# Top.net
KiCad netlist of a schematic drawn in Altium Designer
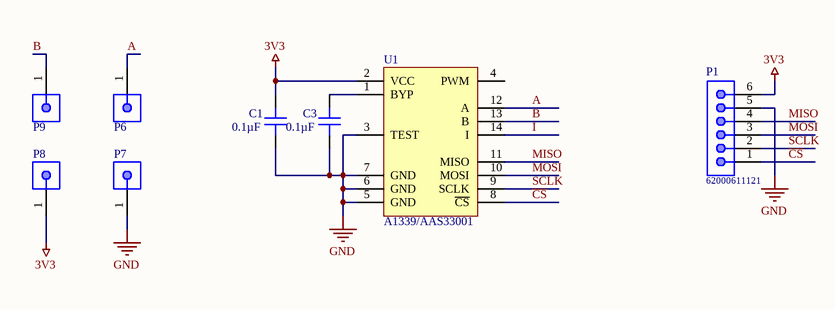
[diagram p0: Top.SchDoc]

(export (version "E")
  (design (tool "Eeschema 10.0.6"))
  (components
    (comp (ref "C1")
      (value "0.1µF")
      (footprint "CAP 0603_1608")
      (description "CAP CER 1UF 10V Y5V 0603")
      (fields
        (field (name "PART NUMBER") "VJ0603V105MXQPW1BC")
        (field (name "MANUFACTURER") "Vishay Vitramon")
      )
      (libsource (lib "Celestial Altium Library - altium_library") (part "Capacitor"))
    )
    (comp (ref "C3")
      (value "0.1µF")
      (footprint "CAP 0603_1608")
      (description "CAP CER 1UF 10V Y5V 0603")
      (fields
        (field (name "PART NUMBER") "VJ0603V105MXQPW1BC")
        (field (name "MANUFACTURER") "Vishay Vitramon")
      )
      (libsource (lib "Celestial Altium Library - altium_library") (part "Capacitor"))
    )
    (comp (ref "P1")
      (value "62000611121")
      (footprint "62000611121")
      (description "WR-PHD Pin Header, THT, pitch 2mm, Single Row, Vertical, 6p")
      (fields (field (name "MANUFACTURER") "Wurth Elektronik"))
      (libsource (lib "Altium_WR-PHD") (part "62000611121"))
    )
    (comp (ref "P6")
      (value "61300111121")
      (footprint "61300111121")
      (description "WR-PHD Pin Header, THT, pitch 2.54mm, Single Row, Vertical, 1p")
      (fields (field (name "MANUFACTURER") "Wurth Elektronik"))
      (libsource (lib "Altium_WR-PHD") (part "61300111121"))
    )
    (comp (ref "P7")
      (value "61300111121")
      (footprint "61300111121")
      (description "WR-PHD Pin Header, THT, pitch 2.54mm, Single Row, Vertical, 1p")
      (fields (field (name "MANUFACTURER") "Wurth Elektronik"))
      (libsource (lib "Altium_WR-PHD") (part "61300111121"))
    )
    (comp (ref "P8")
      (value "61300111121")
      (footprint "61300111121")
      (description "WR-PHD Pin Header, THT, pitch 2.54mm, Single Row, Vertical, 1p")
      (fields (field (name "MANUFACTURER") "Wurth Elektronik"))
      (libsource (lib "Altium_WR-PHD") (part "61300111121"))
    )
    (comp (ref "P9")
      (value "61300111121")
      (footprint "61300111121")
      (description "WR-PHD Pin Header, THT, pitch 2.54mm, Single Row, Vertical, 1p")
      (fields (field (name "MANUFACTURER") "Wurth Elektronik"))
      (libsource (lib "Altium_WR-PHD") (part "61300111121"))
    )
    (comp (ref "U1")
      (value "A1339/AAS33001")
      (footprint "TSSOP14")
      (libsource (lib "IC") (part "A1339/AAS33001"))
    )
  )
  (nets
    (net (code "1") (name "/A") (class "Default")
      (node (ref "P6") (pin "1") (pinfunction "1_1") (pintype "passive"))
      (node (ref "U1") (pin "12") (pinfunction "A_12") (pintype "passive"))
    )
    (net (code "2") (name "/B") (class "Default")
      (node (ref "P9") (pin "1") (pinfunction "1_1") (pintype "passive"))
      (node (ref "U1") (pin "13") (pinfunction "B_13") (pintype "passive"))
    )
    (net (code "3") (name "/I") (class "Default")
      (node (ref "U1") (pin "14") (pinfunction "I_14") (pintype "passive"))
    )
    (net (code "4") (name "/MISO") (class "Default")
      (node (ref "P1") (pin "4") (pinfunction "4_4") (pintype "passive"))
      (node (ref "U1") (pin "11") (pinfunction "MISO_11") (pintype "passive"))
    )
    (net (code "5") (name "/MOSI") (class "Default")
      (node (ref "P1") (pin "3") (pinfunction "3_3") (pintype "passive"))
      (node (ref "U1") (pin "10") (pinfunction "MOSI_10") (pintype "passive"))
    )
    (net (code "6") (name "/SCLK") (class "Default")
      (node (ref "P1") (pin "2") (pinfunction "2_2") (pintype "passive"))
      (node (ref "U1") (pin "9") (pinfunction "SCLK_9") (pintype "passive"))
    )
    (net (code "7") (name "/~{CS}") (class "Default")
      (node (ref "P1") (pin "1") (pinfunction "1_1") (pintype "passive"))
      (node (ref "U1") (pin "8") (pinfunction "~{CS}_8") (pintype "passive"))
    )
    (net (code "8") (name "3V3") (class "Default")
      (node (ref "C1") (pin "1") (pinfunction "1_1") (pintype "passive"))
      (node (ref "P1") (pin "6") (pinfunction "6_6") (pintype "passive"))
      (node (ref "P8") (pin "1") (pinfunction "1_1") (pintype "passive"))
      (node (ref "U1") (pin "2") (pinfunction "VCC_2") (pintype "passive"))
    )
    (net (code "9") (name "GND") (class "Default")
      (node (ref "C1") (pin "2") (pinfunction "2_2") (pintype "passive"))
      (node (ref "C3") (pin "2") (pinfunction "2_2") (pintype "passive"))
      (node (ref "P1") (pin "5") (pinfunction "5_5") (pintype "passive"))
      (node (ref "P7") (pin "1") (pinfunction "1_1") (pintype "passive"))
      (node (ref "U1") (pin "3") (pinfunction "TEST_3") (pintype "passive"))
      (node (ref "U1") (pin "5") (pinfunction "GND_5") (pintype "passive"))
      (node (ref "U1") (pin "6") (pinfunction "GND_6") (pintype "passive"))
      (node (ref "U1") (pin "7") (pinfunction "GND_7") (pintype "passive"))
    )
    (net (code "10") (name "Net-(U1-BYP)") (class "Default")
      (node (ref "C3") (pin "1") (pinfunction "1_1") (pintype "passive"))
      (node (ref "U1") (pin "1") (pinfunction "BYP_1") (pintype "passive"))
    )
    (net (code "11") (name "unconnected-(U1-PWM-Pad4)") (class "Default")
      (node (ref "U1") (pin "4") (pinfunction "PWM_4") (pintype "passive"))
    )
  )
)
